# Aux_Lights_Daughter_REV2_1.net
KiCad netlist of a schematic drawn in Altium Designer
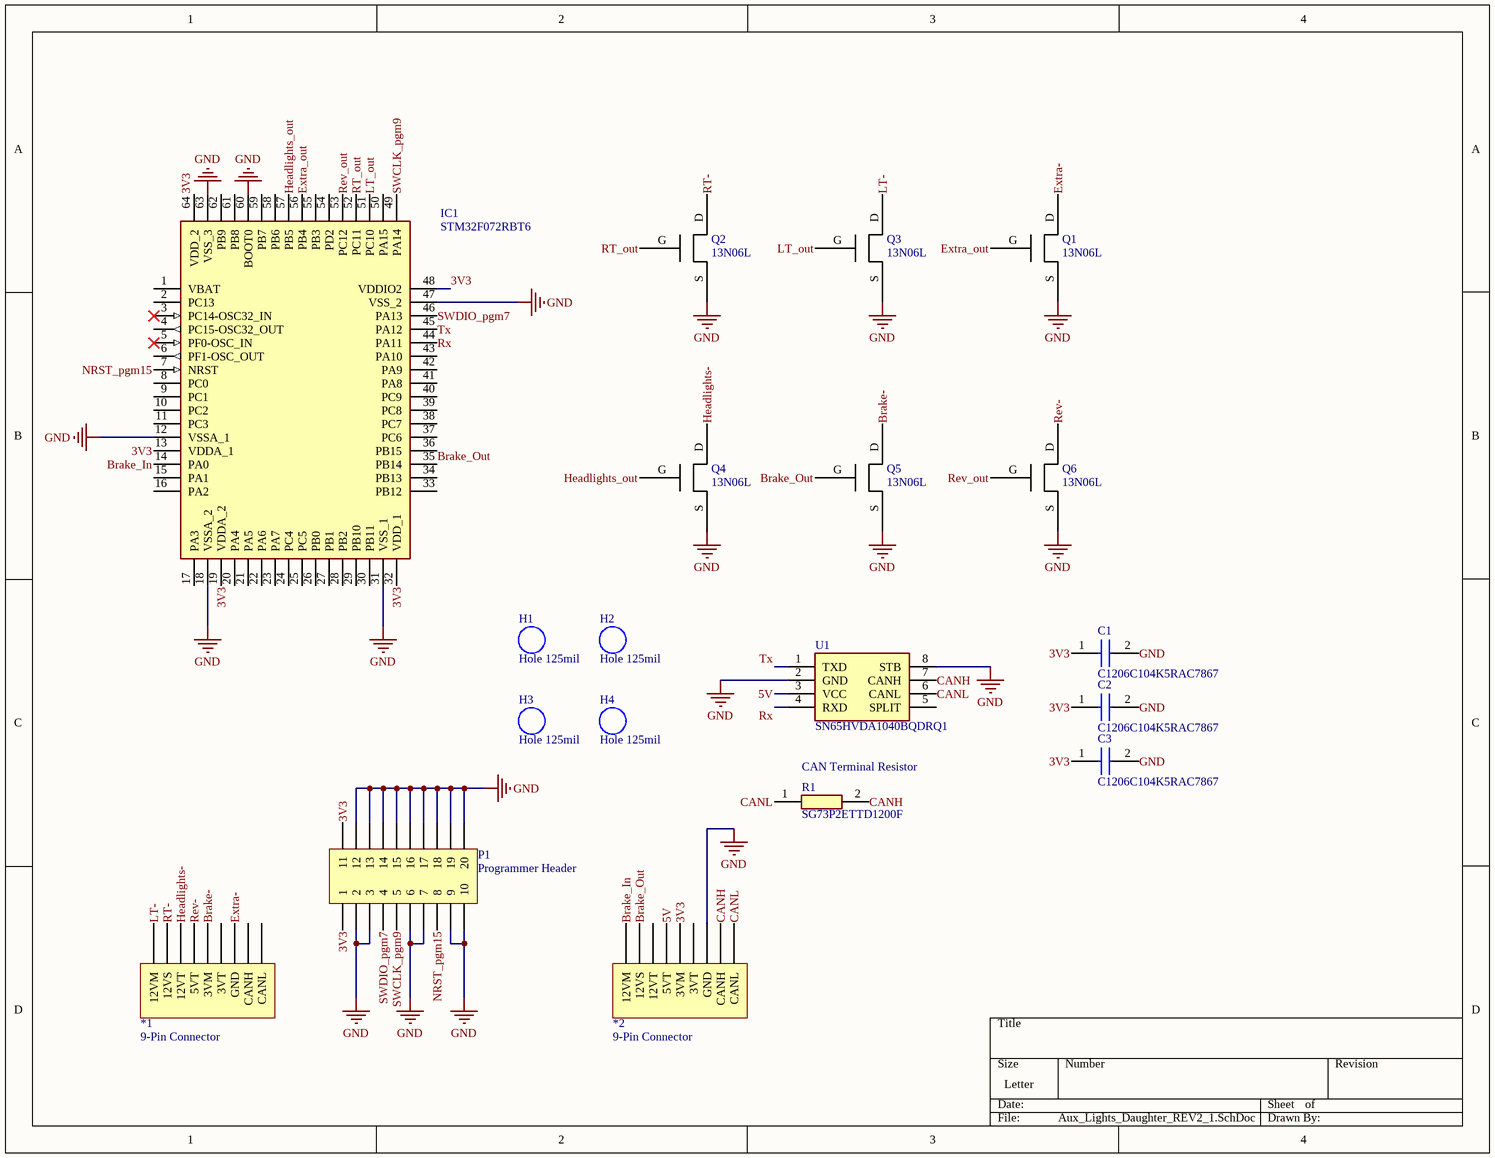
[diagram p0: Aux_Lights_Daughter_REV2_1.SchDoc]

(export (version "E")
  (design (tool "Eeschema 10.0.6"))
  (components
    (comp (ref "*1")
      (value "9-Pin Connector")
      (footprint "9-Pin")
      (libsource (lib "SolarGators") (part "9-Pin Connector"))
    )
    (comp (ref "*2")
      (value "9-Pin Connector")
      (footprint "9-Pin")
      (libsource (lib "SolarGators") (part "9-Pin Connector"))
    )
    (comp (ref "C1")
      (value "C1206C104K5RAC7867")
      (footprint "SamacSys:CAPC3216X110N")
      (description "Capacitor")
      (fields (field (name "MOUSER2 PART NUMBER") "80-C1206104K5RAC7867"))
      (libsource (lib "*") (part "C1206C104K5RAC7867"))
    )
    (comp (ref "C2")
      (value "C1206C104K5RAC7867")
      (footprint "SamacSys:CAPC3216X110N")
      (description "Capacitor")
      (fields (field (name "MOUSER2 PART NUMBER") "80-C1206104K5RAC7867"))
      (libsource (lib "*") (part "C1206C104K5RAC7867"))
    )
    (comp (ref "C3")
      (value "C1206C104K5RAC7867")
      (footprint "SamacSys:CAPC3216X110N")
      (description "Capacitor")
      (fields (field (name "MOUSER2 PART NUMBER") "80-C1206104K5RAC7867"))
      (libsource (lib "*") (part "C1206C104K5RAC7867"))
    )
    (comp (ref "H1")
      (value "Hole 125mil")
      (footprint "Hole 125mil")
      (libsource (lib "ECE LIB new") (part "Hole 125mil"))
    )
    (comp (ref "H2")
      (value "Hole 125mil")
      (footprint "Hole 125mil")
      (libsource (lib "ECE LIB new") (part "Hole 125mil"))
    )
    (comp (ref "H3")
      (value "Hole 125mil")
      (footprint "Hole 125mil")
      (libsource (lib "ECE LIB new") (part "Hole 125mil"))
    )
    (comp (ref "H4")
      (value "Hole 125mil")
      (footprint "Hole 125mil")
      (libsource (lib "ECE LIB new") (part "Hole 125mil"))
    )
    (comp (ref "IC1")
      (value "STM32F072RBT6")
      (footprint "QFP50P1200X1200X160-64N")
      (description "Integrated Circuit")
      (fields (field (name "MOUSER PART NUMBER") "511-STM32F072RBT6"))
      (libsource (lib "solargatorsproject") (part "STM32F072RBT6"))
    )
    (comp (ref "P1")
      (value "Programmer Header")
      (footprint "HDR2X10_CEN")
      (description "Header, 10-Pin, Dual row")
      (fields (field (name "PUBLISHER") "Altium Limited"))
      (libsource (lib "Miscellaneous Connectors") (part "Header 10X2A"))
    )
    (comp (ref "Q1") (value "13N06L") (footprint "13N06L") (libsource (lib "SolarGators") (part "13N06L")))
    (comp (ref "Q2") (value "13N06L") (footprint "13N06L") (libsource (lib "SolarGators") (part "13N06L")))
    (comp (ref "Q3") (value "13N06L") (footprint "13N06L") (libsource (lib "SolarGators") (part "13N06L")))
    (comp (ref "Q4") (value "13N06L") (footprint "13N06L") (libsource (lib "SolarGators") (part "13N06L")))
    (comp (ref "Q5") (value "13N06L") (footprint "13N06L") (libsource (lib "SolarGators") (part "13N06L")))
    (comp (ref "Q6") (value "13N06L") (footprint "13N06L") (libsource (lib "SolarGators") (part "13N06L")))
    (comp (ref "R1")
      (value "SG73P2ETTD1200F")
      (footprint "SamacSys:RESC3226X70N")
      (description "Resistor")
      (libsource (lib "*") (part "SG73P2ETTD1200F"))
    )
    (comp (ref "U1")
      (value "SN65HVDA1040BQDRQ1")
      (footprint "SamacSys:SOIC127P600X175-8N")
      (description "Integrated Circuit")
      (libsource (lib "*") (part "SN65HVDA1040BQDRQ1"))
    )
  )
  (nets
    (net (code "1") (name "/3V3") (class "Default")
      (node (ref "*2") (pin "5") (pinfunction "3VM_5") (pintype "passive"))
      (node (ref "C1") (pin "1") (pinfunction "1_1") (pintype "passive"))
      (node (ref "C2") (pin "1") (pinfunction "1_1") (pintype "passive"))
      (node (ref "C3") (pin "1") (pinfunction "1_1") (pintype "passive"))
      (node (ref "IC1") (pin "13") (pinfunction "VDDA_1_13") (pintype "power_in"))
      (node (ref "IC1") (pin "19") (pinfunction "VDDA_2_19") (pintype "power_in"))
      (node (ref "IC1") (pin "32") (pinfunction "VDD_1_32") (pintype "power_in"))
      (node (ref "IC1") (pin "48") (pinfunction "VDDIO2_48") (pintype "power_in"))
      (node (ref "IC1") (pin "64") (pinfunction "VDD_2_64") (pintype "power_in"))
      (node (ref "P1") (pin "1") (pinfunction "1_1") (pintype "passive"))
      (node (ref "P1") (pin "11") (pinfunction "11_11") (pintype "passive"))
    )
    (net (code "2") (name "/5V") (class "Default")
      (node (ref "*2") (pin "4") (pinfunction "5VT_4") (pintype "passive"))
      (node (ref "U1") (pin "3") (pinfunction "VCC_3") (pintype "passive"))
    )
    (net (code "3") (name "/Brake-") (class "Default")
      (node (ref "*1") (pin "5") (pinfunction "3VM_5") (pintype "passive"))
      (node (ref "Q5") (pin "D") (pinfunction "14_D") (pintype "passive"))
    )
    (net (code "4") (name "/Brake_In") (class "Default")
      (node (ref "*2") (pin "1") (pinfunction "12VM_1") (pintype "passive"))
      (node (ref "IC1") (pin "14") (pinfunction "PA0_14") (pintype "passive"))
    )
    (net (code "5") (name "/Brake_Out") (class "Default")
      (node (ref "*2") (pin "2") (pinfunction "12VS_2") (pintype "passive"))
      (node (ref "IC1") (pin "35") (pinfunction "PB14_35") (pintype "passive"))
      (node (ref "Q5") (pin "G") (pinfunction "13_G") (pintype "passive"))
    )
    (net (code "6") (name "/CANH") (class "Default")
      (node (ref "*2") (pin "8") (pinfunction "CANH_8") (pintype "passive"))
      (node (ref "R1") (pin "2") (pinfunction "2_2") (pintype "passive"))
      (node (ref "U1") (pin "7") (pinfunction "CANH_7") (pintype "passive"))
    )
    (net (code "7") (name "/CANL") (class "Default")
      (node (ref "*2") (pin "9") (pinfunction "CANL_9") (pintype "passive"))
      (node (ref "R1") (pin "1") (pinfunction "1_1") (pintype "passive"))
      (node (ref "U1") (pin "6") (pinfunction "CANL_6") (pintype "passive"))
    )
    (net (code "8") (name "/Extra-") (class "Default")
      (node (ref "*1") (pin "7") (pinfunction "GND_7") (pintype "passive"))
      (node (ref "Q1") (pin "D") (pinfunction "14_D") (pintype "passive"))
    )
    (net (code "9") (name "/Extra_out") (class "Default")
      (node (ref "IC1") (pin "56") (pinfunction "PB4_56") (pintype "passive"))
      (node (ref "Q1") (pin "G") (pinfunction "13_G") (pintype "passive"))
    )
    (net (code "10") (name "/Headlights-") (class "Default")
      (node (ref "*1") (pin "3") (pinfunction "12VT_3") (pintype "passive"))
      (node (ref "Q4") (pin "D") (pinfunction "14_D") (pintype "passive"))
    )
    (net (code "11") (name "/Headlights_out") (class "Default")
      (node (ref "IC1") (pin "57") (pinfunction "PB5_57") (pintype "passive"))
      (node (ref "Q4") (pin "G") (pinfunction "13_G") (pintype "passive"))
    )
    (net (code "12") (name "/LT-") (class "Default")
      (node (ref "*1") (pin "1") (pinfunction "12VM_1") (pintype "passive"))
      (node (ref "Q3") (pin "D") (pinfunction "14_D") (pintype "passive"))
    )
    (net (code "13") (name "/LT_out") (class "Default")
      (node (ref "IC1") (pin "51") (pinfunction "PC10_51") (pintype "passive"))
      (node (ref "Q3") (pin "G") (pinfunction "13_G") (pintype "passive"))
    )
    (net (code "14") (name "/NRST_pgm15") (class "Default")
      (node (ref "IC1") (pin "7") (pinfunction "NRST_7") (pintype "input"))
      (node (ref "P1") (pin "8") (pinfunction "8_8") (pintype "passive"))
    )
    (net (code "15") (name "/RT-") (class "Default")
      (node (ref "*1") (pin "2") (pinfunction "12VS_2") (pintype "passive"))
      (node (ref "Q2") (pin "D") (pinfunction "14_D") (pintype "passive"))
    )
    (net (code "16") (name "/RT_out") (class "Default")
      (node (ref "IC1") (pin "52") (pinfunction "PC11_52") (pintype "passive"))
      (node (ref "Q2") (pin "G") (pinfunction "13_G") (pintype "passive"))
    )
    (net (code "17") (name "/Rev-") (class "Default")
      (node (ref "*1") (pin "4") (pinfunction "5VT_4") (pintype "passive"))
      (node (ref "Q6") (pin "D") (pinfunction "14_D") (pintype "passive"))
    )
    (net (code "18") (name "/Rev_out") (class "Default")
      (node (ref "IC1") (pin "53") (pinfunction "PC12_53") (pintype "passive"))
      (node (ref "Q6") (pin "G") (pinfunction "13_G") (pintype "passive"))
    )
    (net (code "19") (name "/Rx") (class "Default")
      (node (ref "IC1") (pin "44") (pinfunction "PA11_44") (pintype "passive"))
      (node (ref "U1") (pin "4") (pinfunction "RXD_4") (pintype "passive"))
    )
    (net (code "20") (name "/SWCLK_pgm9") (class "Default")
      (node (ref "IC1") (pin "49") (pinfunction "PA14_49") (pintype "passive"))
      (node (ref "P1") (pin "5") (pinfunction "5_5") (pintype "passive"))
    )
    (net (code "21") (name "/SWDIO_pgm7") (class "Default")
      (node (ref "IC1") (pin "46") (pinfunction "PA13_46") (pintype "passive"))
      (node (ref "P1") (pin "4") (pinfunction "4_4") (pintype "passive"))
    )
    (net (code "22") (name "/Tx") (class "Default")
      (node (ref "IC1") (pin "45") (pinfunction "PA12_45") (pintype "passive"))
      (node (ref "U1") (pin "1") (pinfunction "TXD_1") (pintype "passive"))
    )
    (net (code "23") (name "GND") (class "Default")
      (node (ref "*2") (pin "7") (pinfunction "GND_7") (pintype "passive"))
      (node (ref "C1") (pin "2") (pinfunction "2_2") (pintype "passive"))
      (node (ref "C2") (pin "2") (pinfunction "2_2") (pintype "passive"))
      (node (ref "C3") (pin "2") (pinfunction "2_2") (pintype "passive"))
      (node (ref "IC1") (pin "12") (pinfunction "VSSA_1_12") (pintype "power_in"))
      (node (ref "IC1") (pin "18") (pinfunction "VSSA_2_18") (pintype "power_in"))
      (node (ref "IC1") (pin "31") (pinfunction "VSS_1_31") (pintype "power_in"))
      (node (ref "IC1") (pin "47") (pinfunction "VSS_2_47") (pintype "power_in"))
      (node (ref "IC1") (pin "60") (pinfunction "BOOT0_60") (pintype "passive"))
      (node (ref "IC1") (pin "63") (pinfunction "VSS_3_63") (pintype "power_in"))
      (node (ref "P1") (pin "10") (pinfunction "10_10") (pintype "passive"))
      (node (ref "P1") (pin "12") (pinfunction "12_12") (pintype "passive"))
      (node (ref "P1") (pin "13") (pinfunction "13_13") (pintype "passive"))
      (node (ref "P1") (pin "14") (pinfunction "14_14") (pintype "passive"))
      (node (ref "P1") (pin "15") (pinfunction "15_15") (pintype "passive"))
      (node (ref "P1") (pin "16") (pinfunction "16_16") (pintype "passive"))
      (node (ref "P1") (pin "17") (pinfunction "17_17") (pintype "passive"))
      (node (ref "P1") (pin "18") (pinfunction "18_18") (pintype "passive"))
      (node (ref "P1") (pin "19") (pinfunction "19_19") (pintype "passive"))
      (node (ref "P1") (pin "2") (pinfunction "2_2") (pintype "passive"))
      (node (ref "P1") (pin "20") (pinfunction "20_20") (pintype "passive"))
      (node (ref "P1") (pin "3") (pinfunction "3_3") (pintype "passive"))
      (node (ref "P1") (pin "6") (pinfunction "6_6") (pintype "passive"))
      (node (ref "P1") (pin "7") (pinfunction "7_7") (pintype "passive"))
      (node (ref "P1") (pin "9") (pinfunction "9_9") (pintype "passive"))
      (node (ref "Q1") (pin "S") (pinfunction "15_S") (pintype "passive"))
      (node (ref "Q2") (pin "S") (pinfunction "15_S") (pintype "passive"))
      (node (ref "Q3") (pin "S") (pinfunction "15_S") (pintype "passive"))
      (node (ref "Q4") (pin "S") (pinfunction "15_S") (pintype "passive"))
      (node (ref "Q5") (pin "S") (pinfunction "15_S") (pintype "passive"))
      (node (ref "Q6") (pin "S") (pinfunction "15_S") (pintype "passive"))
      (node (ref "U1") (pin "2") (pinfunction "GND_2") (pintype "passive"))
      (node (ref "U1") (pin "8") (pinfunction "STB_8") (pintype "passive"))
    )
    (net (code "24") (name "unconnected-(*1-3VT-Pad6)") (class "Default")
      (node (ref "*1") (pin "6") (pinfunction "3VT_6") (pintype "passive"))
    )
    (net (code "25") (name "unconnected-(*1-CANH-Pad8)") (class "Default")
      (node (ref "*1") (pin "8") (pinfunction "CANH_8") (pintype "passive"))
    )
    (net (code "26") (name "unconnected-(*1-CANL-Pad9)") (class "Default")
      (node (ref "*1") (pin "9") (pinfunction "CANL_9") (pintype "passive"))
    )
    (net (code "27") (name "unconnected-(*2-3VT-Pad6)") (class "Default")
      (node (ref "*2") (pin "6") (pinfunction "3VT_6") (pintype "passive"))
    )
    (net (code "28") (name "unconnected-(*2-12VT-Pad3)") (class "Default")
      (node (ref "*2") (pin "3") (pinfunction "12VT_3") (pintype "passive"))
    )
    (net (code "29") (name "unconnected-(IC1-PA1-Pad15)") (class "Default")
      (node (ref "IC1") (pin "15") (pinfunction "PA1_15") (pintype "passive"))
    )
    (net (code "30") (name "unconnected-(IC1-PA2-Pad16)") (class "Default")
      (node (ref "IC1") (pin "16") (pinfunction "PA2_16") (pintype "passive"))
    )
    (net (code "31") (name "unconnected-(IC1-PA3-Pad17)") (class "Default")
      (node (ref "IC1") (pin "17") (pinfunction "PA3_17") (pintype "passive"))
    )
    (net (code "32") (name "unconnected-(IC1-PA4-Pad20)") (class "Default")
      (node (ref "IC1") (pin "20") (pinfunction "PA4_20") (pintype "passive"))
    )
    (net (code "33") (name "unconnected-(IC1-PA5-Pad21)") (class "Default")
      (node (ref "IC1") (pin "21") (pinfunction "PA5_21") (pintype "passive"))
    )
    (net (code "34") (name "unconnected-(IC1-PA6-Pad22)") (class "Default")
      (node (ref "IC1") (pin "22") (pinfunction "PA6_22") (pintype "passive"))
    )
    (net (code "35") (name "unconnected-(IC1-PA7-Pad23)") (class "Default")
      (node (ref "IC1") (pin "23") (pinfunction "PA7_23") (pintype "passive"))
    )
    (net (code "36") (name "unconnected-(IC1-PA8-Pad41)") (class "Default")
      (node (ref "IC1") (pin "41") (pinfunction "PA8_41") (pintype "passive"))
    )
    (net (code "37") (name "unconnected-(IC1-PA9-Pad42)") (class "Default")
      (node (ref "IC1") (pin "42") (pinfunction "PA9_42") (pintype "passive"))
    )
    (net (code "38") (name "unconnected-(IC1-PA10-Pad43)") (class "Default")
      (node (ref "IC1") (pin "43") (pinfunction "PA10_43") (pintype "passive"))
    )
    (net (code "39") (name "unconnected-(IC1-PA15-Pad50)") (class "Default")
      (node (ref "IC1") (pin "50") (pinfunction "PA15_50") (pintype "passive"))
    )
    (net (code "40") (name "unconnected-(IC1-PB0-Pad26)") (class "Default")
      (node (ref "IC1") (pin "26") (pinfunction "PB0_26") (pintype "passive"))
    )
    (net (code "41") (name "unconnected-(IC1-PB1-Pad27)") (class "Default")
      (node (ref "IC1") (pin "27") (pinfunction "PB1_27") (pintype "passive"))
    )
    (net (code "42") (name "unconnected-(IC1-PB2-Pad28)") (class "Default")
      (node (ref "IC1") (pin "28") (pinfunction "PB2_28") (pintype "passive"))
    )
    (net (code "43") (name "unconnected-(IC1-PB3-Pad55)") (class "Default")
      (node (ref "IC1") (pin "55") (pinfunction "PB3_55") (pintype "passive"))
    )
    (net (code "44") (name "unconnected-(IC1-PB6-Pad58)") (class "Default")
      (node (ref "IC1") (pin "58") (pinfunction "PB6_58") (pintype "passive"))
    )
    (net (code "45") (name "unconnected-(IC1-PB7-Pad59)") (class "Default")
      (node (ref "IC1") (pin "59") (pinfunction "PB7_59") (pintype "passive"))
    )
    (net (code "46") (name "unconnected-(IC1-PB8-Pad61)") (class "Default")
      (node (ref "IC1") (pin "61") (pinfunction "PB8_61") (pintype "passive"))
    )
    (net (code "47") (name "unconnected-(IC1-PB9-Pad62)") (class "Default")
      (node (ref "IC1") (pin "62") (pinfunction "PB9_62") (pintype "passive"))
    )
    (net (code "48") (name "unconnected-(IC1-PB10-Pad29)") (class "Default")
      (node (ref "IC1") (pin "29") (pinfunction "PB10_29") (pintype "passive"))
    )
    (net (code "49") (name "unconnected-(IC1-PB11-Pad30)") (class "Default")
      (node (ref "IC1") (pin "30") (pinfunction "PB11_30") (pintype "passive"))
    )
    (net (code "50") (name "unconnected-(IC1-PB12-Pad33)") (class "Default")
      (node (ref "IC1") (pin "33") (pinfunction "PB12_33") (pintype "passive"))
    )
    (net (code "51") (name "unconnected-(IC1-PB13-Pad34)") (class "Default")
      (node (ref "IC1") (pin "34") (pinfunction "PB13_34") (pintype "passive"))
    )
    (net (code "52") (name "unconnected-(IC1-PB15-Pad36)") (class "Default")
      (node (ref "IC1") (pin "36") (pinfunction "PB15_36") (pintype "passive"))
    )
    (net (code "53") (name "unconnected-(IC1-PC0-Pad8)") (class "Default")
      (node (ref "IC1") (pin "8") (pinfunction "PC0_8") (pintype "passive"))
    )
    (net (code "54") (name "unconnected-(IC1-PC1-Pad9)") (class "Default")
      (node (ref "IC1") (pin "9") (pinfunction "PC1_9") (pintype "passive"))
    )
    (net (code "55") (name "unconnected-(IC1-PC2-Pad10)") (class "Default")
      (node (ref "IC1") (pin "10") (pinfunction "PC2_10") (pintype "passive"))
    )
    (net (code "56") (name "unconnected-(IC1-PC3-Pad11)") (class "Default")
      (node (ref "IC1") (pin "11") (pinfunction "PC3_11") (pintype "passive"))
    )
    (net (code "57") (name "unconnected-(IC1-PC4-Pad24)") (class "Default")
      (node (ref "IC1") (pin "24") (pinfunction "PC4_24") (pintype "passive"))
    )
    (net (code "58") (name "unconnected-(IC1-PC5-Pad25)") (class "Default")
      (node (ref "IC1") (pin "25") (pinfunction "PC5_25") (pintype "passive"))
    )
    (net (code "59") (name "unconnected-(IC1-PC6-Pad37)") (class "Default")
      (node (ref "IC1") (pin "37") (pinfunction "PC6_37") (pintype "passive"))
    )
    (net (code "60") (name "unconnected-(IC1-PC7-Pad38)") (class "Default")
      (node (ref "IC1") (pin "38") (pinfunction "PC7_38") (pintype "passive"))
    )
    (net (code "61") (name "unconnected-(IC1-PC8-Pad39)") (class "Default")
      (node (ref "IC1") (pin "39") (pinfunction "PC8_39") (pintype "passive"))
    )
    (net (code "62") (name "unconnected-(IC1-PC9-Pad40)") (class "Default")
      (node (ref "IC1") (pin "40") (pinfunction "PC9_40") (pintype "passive"))
    )
    (net (code "63") (name "unconnected-(IC1-PC13-Pad2)") (class "Default")
      (node (ref "IC1") (pin "2") (pinfunction "PC13_2") (pintype "passive"))
    )
    (net (code "64") (name "unconnected-(IC1-PC14-OSC32_IN-Pad3)") (class "Default")
      (node (ref "IC1") (pin "3") (pinfunction "PC14-OSC32_IN_3") (pintype "input+no_connect"))
    )
    (net (code "65") (name "unconnected-(IC1-PC15-OSC32_OUT-Pad4)") (class "Default")
      (node (ref "IC1") (pin "4") (pinfunction "PC15-OSC32_OUT_4") (pintype "output"))
    )
    (net (code "66") (name "unconnected-(IC1-PD2-Pad54)") (class "Default")
      (node (ref "IC1") (pin "54") (pinfunction "PD2_54") (pintype "passive"))
    )
    (net (code "67") (name "unconnected-(IC1-PF0-OSC_IN-Pad5)") (class "Default")
      (node (ref "IC1") (pin "5") (pinfunction "PF0-OSC_IN_5") (pintype "input+no_connect"))
    )
    (net (code "68") (name "unconnected-(IC1-PF1-OSC_OUT-Pad6)") (class "Default")
      (node (ref "IC1") (pin "6") (pinfunction "PF1-OSC_OUT_6") (pintype "output"))
    )
    (net (code "69") (name "unconnected-(IC1-VBAT-Pad1)") (class "Default")
      (node (ref "IC1") (pin "1") (pinfunction "VBAT_1") (pintype "passive"))
    )
    (net (code "70") (name "unconnected-(U1-SPLIT-Pad5)") (class "Default")
      (node (ref "U1") (pin "5") (pinfunction "SPLIT_5") (pintype "passive"))
    )
  )
)
